# Nguyen_Ly.net
KiCad netlist of a schematic drawn in Altium Designer
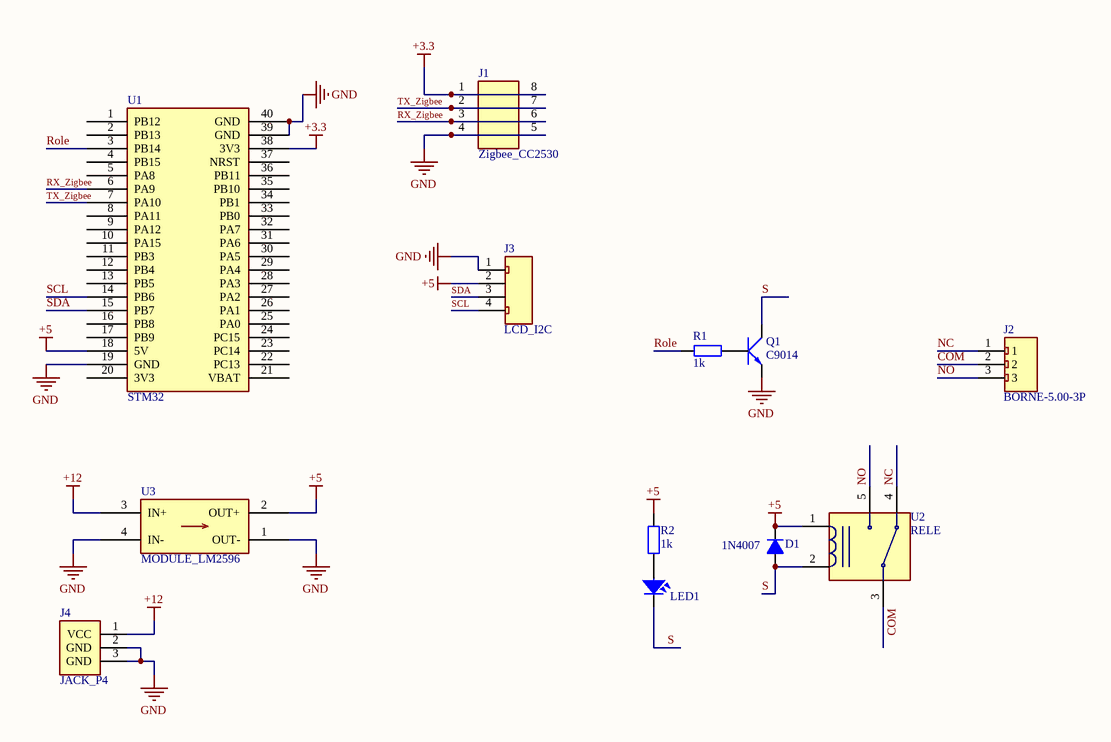
[diagram p0: Nguyen_Ly.SchDoc]

(export (version "E")
  (design (tool "Eeschema 10.0.6"))
  (components
    (comp (ref "D1")
      (value "1N4007")
      (footprint "D1A")
      (description "Diode 1A")
      (libsource (lib "Thuvien3D") (part "D1A"))
    )
    (comp (ref "J1")
      (value "Zigbee_CC2530")
      (footprint "FEMALE-2.54-4x2P")
      (description "Female Header Connector 2.54mm 4x2 Pins.")
      (libsource (lib "Connectors") (part "FEMALE-2.54-4x2P"))
    )
    (comp (ref "J2")
      (value "BORNE-5.00-3P")
      (footprint "BORNE-5.00-3P")
      (description "Borne 3 Vias, Pitch 5mm.")
      (libsource (lib "Connectors") (part "BORNE-5.00-3P"))
    )
    (comp (ref "J3")
      (value "LCD_I2C")
      (footprint "JST-2.00-4P")
      (description "Female Connector JST 4 Vias, 2.00mm.")
      (libsource (lib "Connectors") (part "JST-2.00-4P"))
    )
    (comp (ref "J4")
      (value "JACK_P4")
      (footprint "JACK_P4")
      (description "9V Battery Connector Jack P4.")
      (libsource (lib "Connectors") (part "JACK_P4"))
    )
    (comp (ref "LED1")
      (value "LED")
      (footprint "LED-3")
      (description "LED Single colour Green and Red")
      (libsource (lib "Thuvien3D") (part "LED"))
    )
    (comp (ref "Q1")
      (value "C9014")
      (footprint "QTO-92")
      (description "P 600mW, EBC")
      (libsource (lib "Thuvien3D") (part "NPN_EBC"))
    )
    (comp (ref "R1")
      (value "1k")
      (footprint "R1/4W")
      (description "Resistor 1/4W")
      (libsource (lib "Thuvien3D") (part "R1/4W"))
    )
    (comp (ref "R2")
      (value "1k")
      (footprint "R1/4W")
      (description "Resistor 1/4W")
      (libsource (lib "Thuvien3D") (part "R1/4W"))
    )
    (comp (ref "U1")
      (value "STM32")
      (footprint "STM32")
      (libsource (lib "Other Microcontrollers") (part "STM32"))
    )
    (comp (ref "U2")
      (value "RELE")
      (footprint "RELE")
      (description "Generic Rele PTH 5 Pins.")
      (libsource (lib "Random") (part "RELE"))
    )
    (comp (ref "U3")
      (value "MODULE_LM2596")
      (footprint "MODULE_LM2596")
      (description "MODULE BUCK STEP DOWN 3A 43x20mm")
      (libsource (lib "Voltage Regulators") (part "MODULE_LM2596"))
    )
  )
  (nets
    (net (code "1") (name "+3.3") (class "Default")
      (node (ref "J1") (pin "1") (pintype "passive"))
      (node (ref "J1") (pin "8") (pintype "passive"))
      (node (ref "U1") (pin "38") (pinfunction "3V3_38") (pintype "passive"))
    )
    (net (code "2") (name "+5") (class "Default")
      (node (ref "D1") (pin "2") (pinfunction "K_2") (pintype "passive"))
      (node (ref "J3") (pin "2") (pintype "passive"))
      (node (ref "R2") (pin "2") (pinfunction "2_2") (pintype "passive"))
      (node (ref "U1") (pin "18") (pinfunction "5V_18") (pintype "passive"))
      (node (ref "U2") (pin "1") (pintype "passive"))
      (node (ref "U3") (pin "2") (pinfunction "OUT+_2") (pintype "passive"))
    )
    (net (code "3") (name "+12") (class "Default")
      (node (ref "J4") (pin "1") (pinfunction "VCC_1") (pintype "passive"))
      (node (ref "U3") (pin "3") (pinfunction "IN+_3") (pintype "passive"))
    )
    (net (code "4") (name "/COM") (class "Default")
      (node (ref "J2") (pin "2") (pinfunction "2_2") (pintype "passive"))
      (node (ref "U2") (pin "3") (pintype "passive"))
    )
    (net (code "5") (name "/NC") (class "Default")
      (node (ref "J2") (pin "1") (pinfunction "1_1") (pintype "passive"))
      (node (ref "U2") (pin "4") (pintype "passive"))
    )
    (net (code "6") (name "/NO") (class "Default")
      (node (ref "J2") (pin "3") (pinfunction "3_3") (pintype "passive"))
      (node (ref "U2") (pin "5") (pintype "passive"))
    )
    (net (code "7") (name "/RX_Zigbee") (class "Default")
      (node (ref "J1") (pin "3") (pintype "passive"))
      (node (ref "J1") (pin "6") (pintype "passive"))
      (node (ref "U1") (pin "6") (pinfunction "PA9_6") (pintype "passive"))
    )
    (net (code "8") (name "/Role") (class "Default")
      (node (ref "R1") (pin "1") (pinfunction "1_1") (pintype "passive"))
      (node (ref "U1") (pin "3") (pinfunction "PB14_3") (pintype "passive"))
    )
    (net (code "9") (name "/S") (class "Default")
      (node (ref "D1") (pin "1") (pinfunction "A_1") (pintype "passive"))
      (node (ref "LED1") (pin "2") (pinfunction "2_2") (pintype "passive"))
      (node (ref "Q1") (pin "3") (pinfunction "C_3") (pintype "passive"))
      (node (ref "U2") (pin "2") (pintype "passive"))
    )
    (net (code "10") (name "/SCL") (class "Default")
      (node (ref "J3") (pin "4") (pintype "passive"))
      (node (ref "U1") (pin "14") (pinfunction "PB6_14") (pintype "passive"))
    )
    (net (code "11") (name "/SDA") (class "Default")
      (node (ref "J3") (pin "3") (pintype "passive"))
      (node (ref "U1") (pin "15") (pinfunction "PB7_15") (pintype "passive"))
    )
    (net (code "12") (name "/TX_Zigbee") (class "Default")
      (node (ref "J1") (pin "2") (pintype "passive"))
      (node (ref "J1") (pin "7") (pintype "passive"))
      (node (ref "U1") (pin "7") (pinfunction "PA10_7") (pintype "passive"))
    )
    (net (code "13") (name "GND") (class "Default")
      (node (ref "J1") (pin "4") (pintype "passive"))
      (node (ref "J1") (pin "5") (pintype "passive"))
      (node (ref "J3") (pin "1") (pintype "passive"))
      (node (ref "J4") (pin "2") (pinfunction "GND_2") (pintype "passive"))
      (node (ref "J4") (pin "3") (pinfunction "GND_3") (pintype "passive"))
      (node (ref "Q1") (pin "1") (pinfunction "E_1") (pintype "passive"))
      (node (ref "U1") (pin "19") (pinfunction "GND_19") (pintype "passive"))
      (node (ref "U1") (pin "39") (pinfunction "GND_39") (pintype "passive"))
      (node (ref "U1") (pin "40") (pinfunction "GND_40") (pintype "passive"))
      (node (ref "U3") (pin "1") (pinfunction "OUT-_1") (pintype "passive"))
      (node (ref "U3") (pin "4") (pinfunction "IN-_4") (pintype "passive"))
    )
    (net (code "14") (name "Net-(LED1-Pad1)") (class "Default")
      (node (ref "LED1") (pin "1") (pinfunction "1_1") (pintype "passive"))
      (node (ref "R2") (pin "1") (pinfunction "1_1") (pintype "passive"))
    )
    (net (code "15") (name "Net-(Q1-B)") (class "Default")
      (node (ref "Q1") (pin "2") (pinfunction "B_2") (pintype "passive"))
      (node (ref "R1") (pin "2") (pinfunction "2_2") (pintype "passive"))
    )
    (net (code "16") (name "unconnected-(U1-3V3-Pad20)") (class "Default")
      (node (ref "U1") (pin "20") (pinfunction "3V3_20") (pintype "passive"))
    )
    (net (code "17") (name "unconnected-(U1-NRST-Pad37)") (class "Default")
      (node (ref "U1") (pin "37") (pinfunction "NRST_37") (pintype "passive"))
    )
    (net (code "18") (name "unconnected-(U1-PA0-Pad25)") (class "Default")
      (node (ref "U1") (pin "25") (pinfunction "PA0_25") (pintype "passive"))
    )
    (net (code "19") (name "unconnected-(U1-PA1-Pad26)") (class "Default")
      (node (ref "U1") (pin "26") (pinfunction "PA1_26") (pintype "passive"))
    )
    (net (code "20") (name "unconnected-(U1-PA2-Pad27)") (class "Default")
      (node (ref "U1") (pin "27") (pinfunction "PA2_27") (pintype "passive"))
    )
    (net (code "21") (name "unconnected-(U1-PA3-Pad28)") (class "Default")
      (node (ref "U1") (pin "28") (pinfunction "PA3_28") (pintype "passive"))
    )
    (net (code "22") (name "unconnected-(U1-PA4-Pad29)") (class "Default")
      (node (ref "U1") (pin "29") (pinfunction "PA4_29") (pintype "passive"))
    )
    (net (code "23") (name "unconnected-(U1-PA5-Pad30)") (class "Default")
      (node (ref "U1") (pin "30") (pinfunction "PA5_30") (pintype "passive"))
    )
    (net (code "24") (name "unconnected-(U1-PA6-Pad31)") (class "Default")
      (node (ref "U1") (pin "31") (pinfunction "PA6_31") (pintype "passive"))
    )
    (net (code "25") (name "unconnected-(U1-PA7-Pad32)") (class "Default")
      (node (ref "U1") (pin "32") (pinfunction "PA7_32") (pintype "passive"))
    )
    (net (code "26") (name "unconnected-(U1-PA8-Pad5)") (class "Default")
      (node (ref "U1") (pin "5") (pinfunction "PA8_5") (pintype "passive"))
    )
    (net (code "27") (name "unconnected-(U1-PA11-Pad8)") (class "Default")
      (node (ref "U1") (pin "8") (pinfunction "PA11_8") (pintype "passive"))
    )
    (net (code "28") (name "unconnected-(U1-PA12-Pad9)") (class "Default")
      (node (ref "U1") (pin "9") (pinfunction "PA12_9") (pintype "passive"))
    )
    (net (code "29") (name "unconnected-(U1-PA15-Pad10)") (class "Default")
      (node (ref "U1") (pin "10") (pinfunction "PA15_10") (pintype "passive"))
    )
    (net (code "30") (name "unconnected-(U1-PB0-Pad33)") (class "Default")
      (node (ref "U1") (pin "33") (pinfunction "PB0_33") (pintype "passive"))
    )
    (net (code "31") (name "unconnected-(U1-PB1-Pad34)") (class "Default")
      (node (ref "U1") (pin "34") (pinfunction "PB1_34") (pintype "passive"))
    )
    (net (code "32") (name "unconnected-(U1-PB3-Pad11)") (class "Default")
      (node (ref "U1") (pin "11") (pinfunction "PB3_11") (pintype "passive"))
    )
    (net (code "33") (name "unconnected-(U1-PB4-Pad12)") (class "Default")
      (node (ref "U1") (pin "12") (pinfunction "PB4_12") (pintype "passive"))
    )
    (net (code "34") (name "unconnected-(U1-PB5-Pad13)") (class "Default")
      (node (ref "U1") (pin "13") (pinfunction "PB5_13") (pintype "passive"))
    )
    (net (code "35") (name "unconnected-(U1-PB8-Pad16)") (class "Default")
      (node (ref "U1") (pin "16") (pinfunction "PB8_16") (pintype "passive"))
    )
    (net (code "36") (name "unconnected-(U1-PB9-Pad17)") (class "Default")
      (node (ref "U1") (pin "17") (pinfunction "PB9_17") (pintype "passive"))
    )
    (net (code "37") (name "unconnected-(U1-PB10-Pad35)") (class "Default")
      (node (ref "U1") (pin "35") (pinfunction "PB10_35") (pintype "passive"))
    )
    (net (code "38") (name "unconnected-(U1-PB11-Pad36)") (class "Default")
      (node (ref "U1") (pin "36") (pinfunction "PB11_36") (pintype "passive"))
    )
    (net (code "39") (name "unconnected-(U1-PB12-Pad1)") (class "Default")
      (node (ref "U1") (pin "1") (pinfunction "PB12_1") (pintype "passive"))
    )
    (net (code "40") (name "unconnected-(U1-PB13-Pad2)") (class "Default")
      (node (ref "U1") (pin "2") (pinfunction "PB13_2") (pintype "passive"))
    )
    (net (code "41") (name "unconnected-(U1-PB15-Pad4)") (class "Default")
      (node (ref "U1") (pin "4") (pinfunction "PB15_4") (pintype "passive"))
    )
    (net (code "42") (name "unconnected-(U1-PC13-Pad22)") (class "Default")
      (node (ref "U1") (pin "22") (pinfunction "PC13_22") (pintype "passive"))
    )
    (net (code "43") (name "unconnected-(U1-PC14-Pad23)") (class "Default")
      (node (ref "U1") (pin "23") (pinfunction "PC14_23") (pintype "passive"))
    )
    (net (code "44") (name "unconnected-(U1-PC15-Pad24)") (class "Default")
      (node (ref "U1") (pin "24") (pinfunction "PC15_24") (pintype "passive"))
    )
    (net (code "45") (name "unconnected-(U1-VBAT-Pad21)") (class "Default")
      (node (ref "U1") (pin "21") (pinfunction "VBAT_21") (pintype "passive"))
    )
  )
)
